# Witch.net
KiCad netlist of a schematic drawn in EAGLE
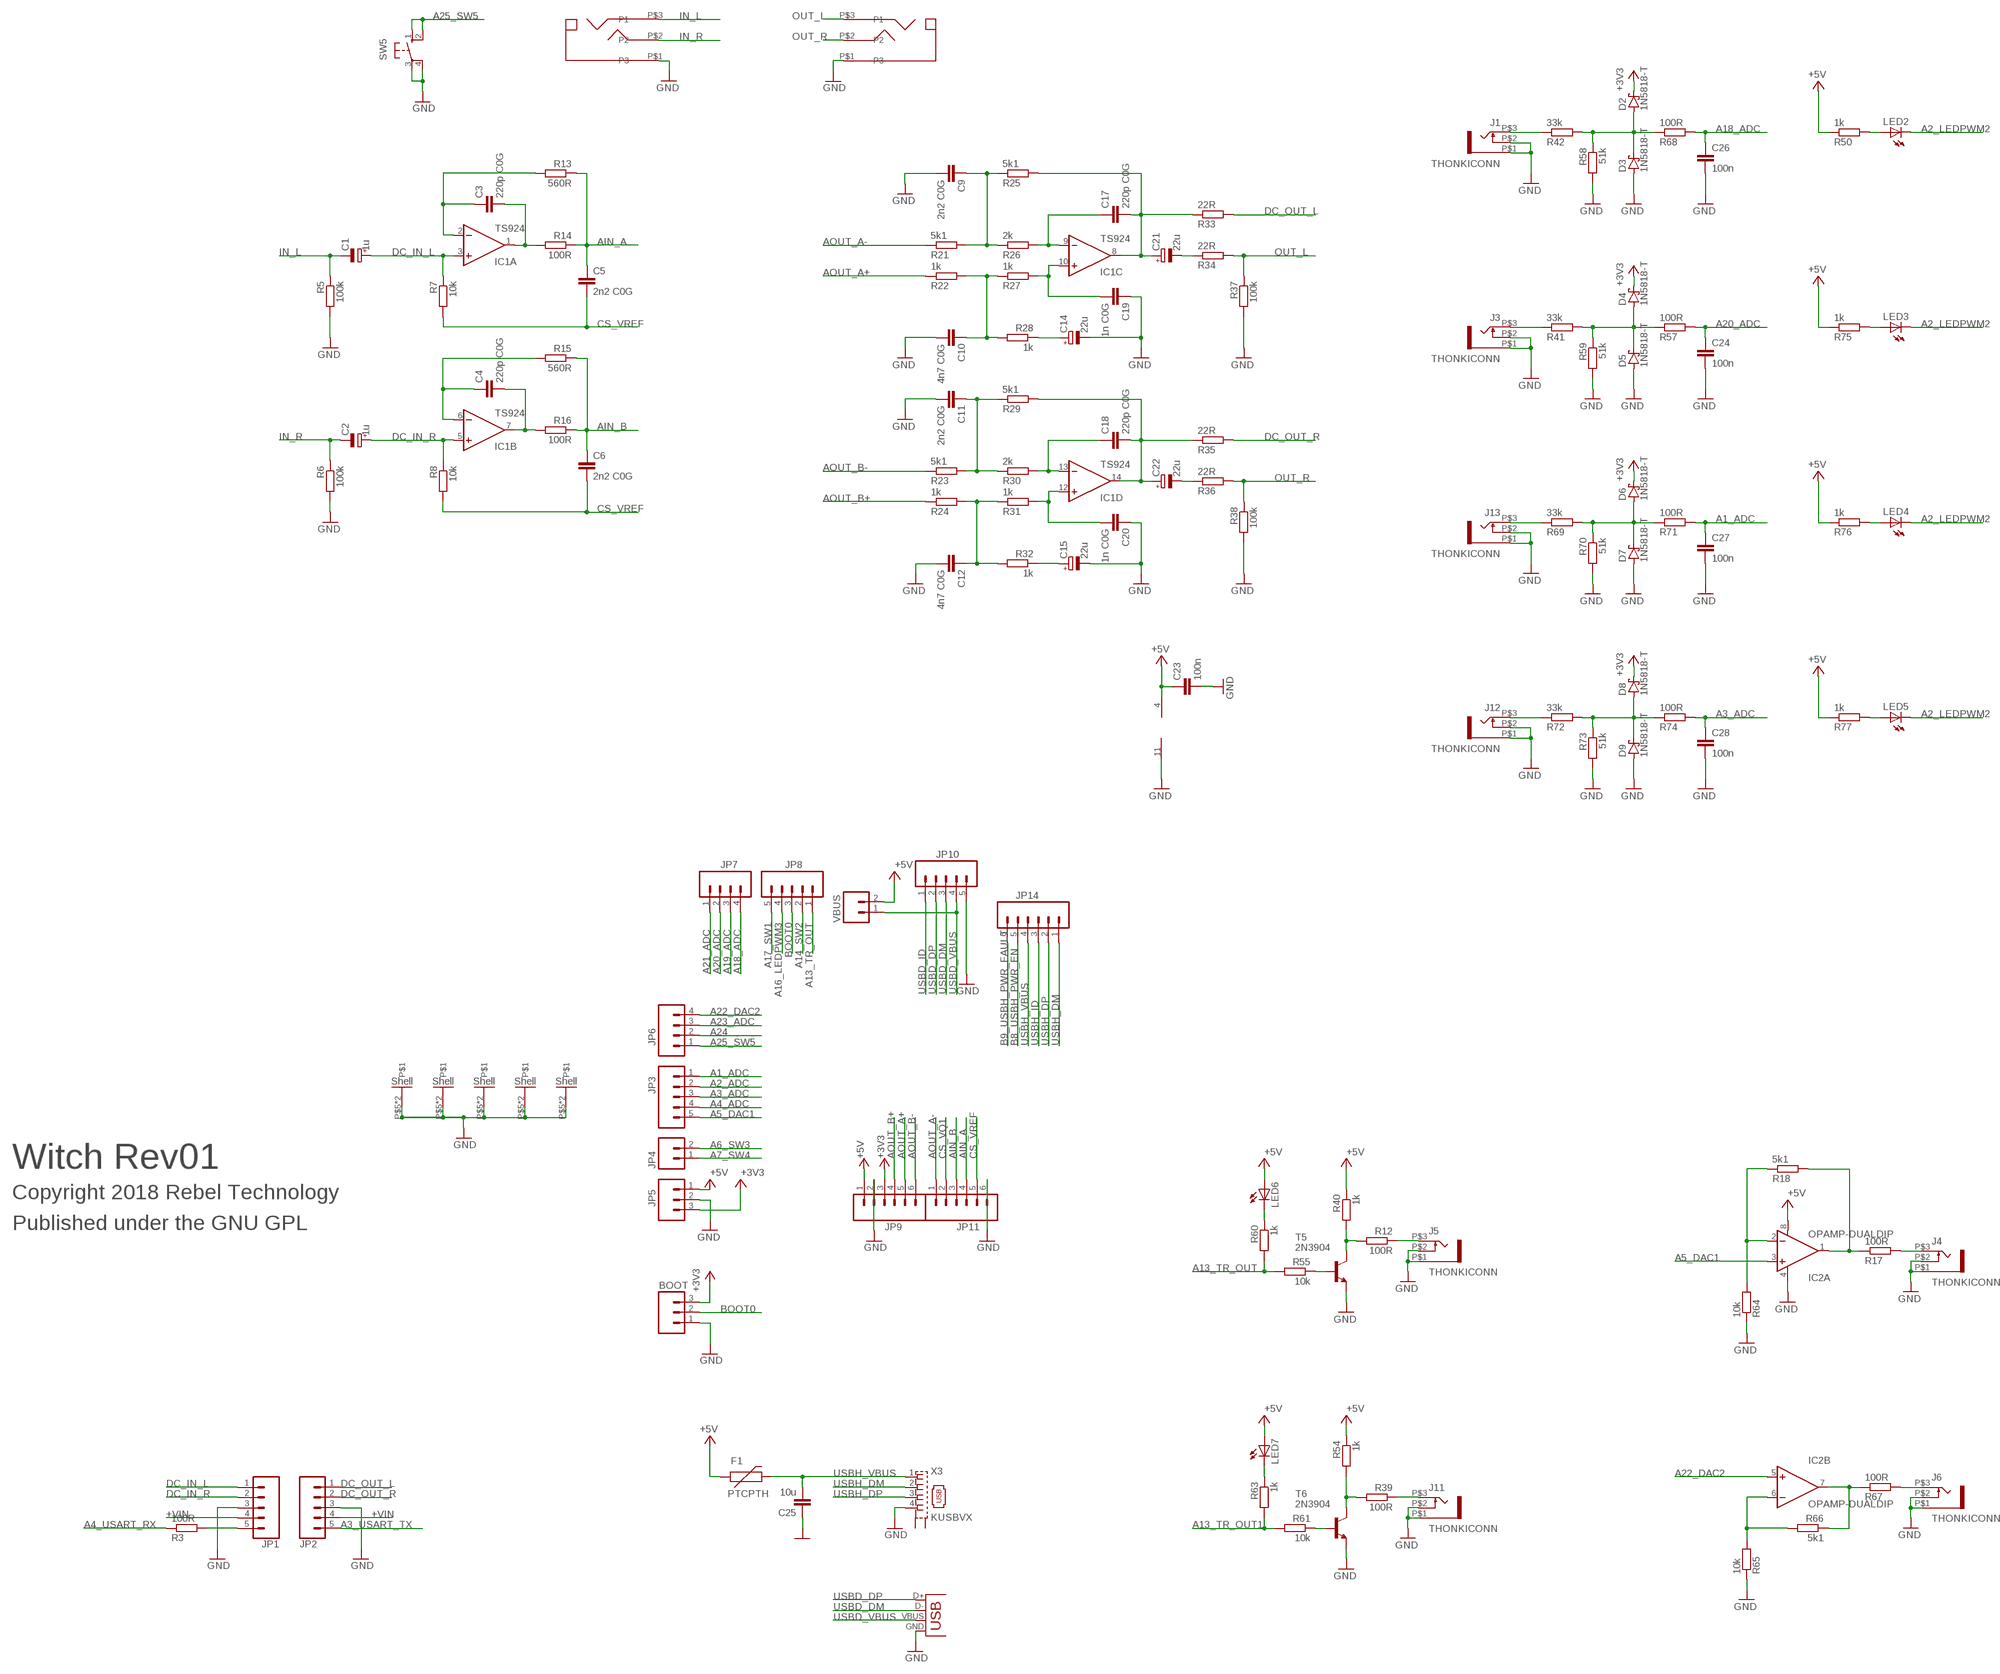
[diagram p0: schematic, sheet 1, part 1 of 2]
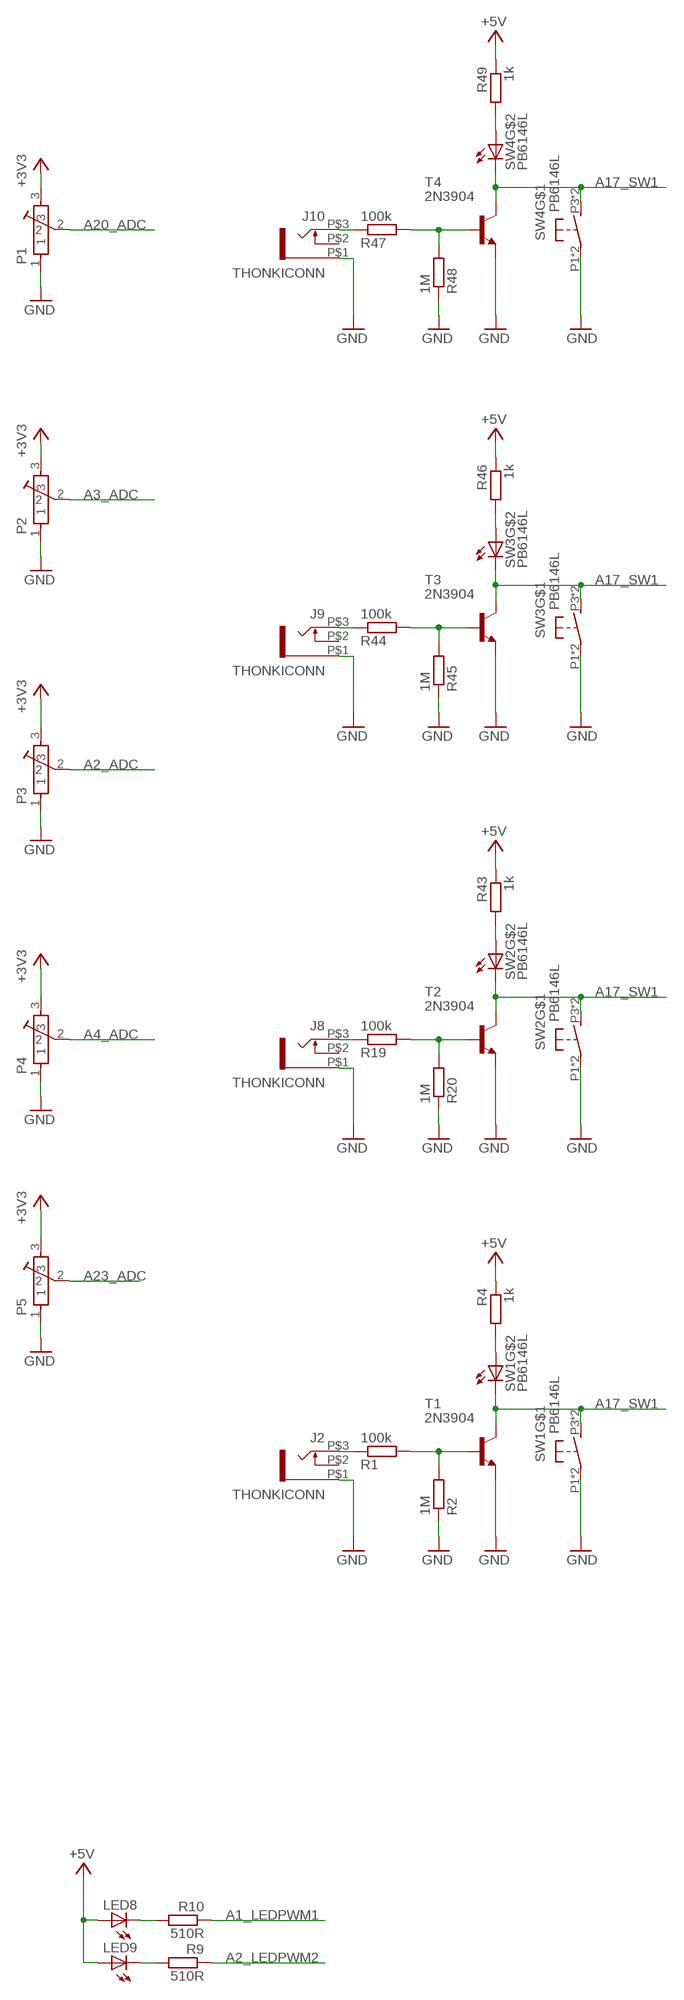
[diagram p1: schematic, sheet 1, part 2 of 2]

(export (version "E")
  (design (tool "Eeschema 10.0.6"))
  (components
    (comp (ref "BOOT")
      (value "M03PTH")
      (footprint "eagle-import:1X03")
      (libsource (lib "eagle-import") (part "M03PTH"))
    )
    (comp (ref "C1")
      (value "1u")
      (footprint "eagle-import:E5-6")
      (libsource (lib "eagle-import") (part "CPOL-EUE5-6"))
    )
    (comp (ref "C2")
      (value "1u")
      (footprint "eagle-import:E5-6")
      (libsource (lib "eagle-import") (part "CPOL-EUE5-6"))
    )
    (comp (ref "C3")
      (value "220p C0G")
      (footprint "eagle-import:C050-024X044")
      (libsource (lib "eagle-import") (part "C-EU050-024X044"))
    )
    (comp (ref "C4")
      (value "220p C0G")
      (footprint "eagle-import:C050-024X044")
      (libsource (lib "eagle-import") (part "C-EU050-024X044"))
    )
    (comp (ref "C5")
      (value "2n2 C0G")
      (footprint "eagle-import:C050-024X044")
      (libsource (lib "eagle-import") (part "C-EU050-024X044"))
    )
    (comp (ref "C6")
      (value "2n2 C0G")
      (footprint "eagle-import:C050-024X044")
      (libsource (lib "eagle-import") (part "C-EU050-024X044"))
    )
    (comp (ref "C9")
      (value "2n2 C0G")
      (footprint "eagle-import:C050-024X044")
      (libsource (lib "eagle-import") (part "C-EU050-024X044"))
    )
    (comp (ref "C10")
      (value "4n7 C0G")
      (footprint "eagle-import:C050-024X044")
      (libsource (lib "eagle-import") (part "C-EU050-024X044"))
    )
    (comp (ref "C11")
      (value "2n2 C0G")
      (footprint "eagle-import:C050-024X044")
      (libsource (lib "eagle-import") (part "C-EU050-024X044"))
    )
    (comp (ref "C12")
      (value "4n7 C0G")
      (footprint "eagle-import:C050-024X044")
      (libsource (lib "eagle-import") (part "C-EU050-024X044"))
    )
    (comp (ref "C14")
      (value "22u")
      (footprint "eagle-import:E5-6")
      (libsource (lib "eagle-import") (part "CPOL-EUE5-6"))
    )
    (comp (ref "C15")
      (value "22u")
      (footprint "eagle-import:E5-6")
      (libsource (lib "eagle-import") (part "CPOL-EUE5-6"))
    )
    (comp (ref "C17")
      (value "220p C0G")
      (footprint "eagle-import:C050-024X044")
      (libsource (lib "eagle-import") (part "C-EU050-024X044"))
    )
    (comp (ref "C18")
      (value "220p C0G")
      (footprint "eagle-import:C050-024X044")
      (libsource (lib "eagle-import") (part "C-EU050-024X044"))
    )
    (comp (ref "C19")
      (value "1n C0G")
      (footprint "eagle-import:C050-024X044")
      (libsource (lib "eagle-import") (part "C-EU050-024X044"))
    )
    (comp (ref "C20")
      (value "1n C0G")
      (footprint "eagle-import:C050-024X044")
      (libsource (lib "eagle-import") (part "C-EU050-024X044"))
    )
    (comp (ref "C21")
      (value "22u")
      (footprint "eagle-import:E5-6")
      (libsource (lib "eagle-import") (part "CPOL-EUE5-6"))
    )
    (comp (ref "C22")
      (value "22u")
      (footprint "eagle-import:E5-6")
      (libsource (lib "eagle-import") (part "CPOL-EUE5-6"))
    )
    (comp (ref "C23")
      (value "100n")
      (footprint "eagle-import:C050-024X044")
      (libsource (lib "eagle-import") (part "C-EU050-024X044"))
    )
    (comp (ref "C24")
      (value "100n")
      (footprint "eagle-import:C050-024X044")
      (libsource (lib "eagle-import") (part "C-EU050-024X044"))
    )
    (comp (ref "C25")
      (value "10u")
      (footprint "eagle-import:C050-024X044")
      (libsource (lib "eagle-import") (part "C-EU050-024X044"))
    )
    (comp (ref "C26")
      (value "100n")
      (footprint "eagle-import:C050-024X044")
      (libsource (lib "eagle-import") (part "C-EU050-024X044"))
    )
    (comp (ref "C27")
      (value "100n")
      (footprint "eagle-import:C050-024X044")
      (libsource (lib "eagle-import") (part "C-EU050-024X044"))
    )
    (comp (ref "C28")
      (value "100n")
      (footprint "eagle-import:C050-024X044")
      (libsource (lib "eagle-import") (part "C-EU050-024X044"))
    )
    (comp (ref "D2")
      (value "1N5818-T")
      (footprint "eagle-import:DO41-7.6")
      (libsource (lib "eagle-import") (part "1N5818-T"))
    )
    (comp (ref "D3")
      (value "1N5818-T")
      (footprint "eagle-import:DO41-7.6")
      (libsource (lib "eagle-import") (part "1N5818-T"))
    )
    (comp (ref "D4")
      (value "1N5818-T")
      (footprint "eagle-import:DO41-7.6")
      (libsource (lib "eagle-import") (part "1N5818-T"))
    )
    (comp (ref "D5")
      (value "1N5818-T")
      (footprint "eagle-import:DO41-7.6")
      (libsource (lib "eagle-import") (part "1N5818-T"))
    )
    (comp (ref "D6")
      (value "1N5818-T")
      (footprint "eagle-import:DO41-7.6")
      (libsource (lib "eagle-import") (part "1N5818-T"))
    )
    (comp (ref "D7")
      (value "1N5818-T")
      (footprint "eagle-import:DO41-7.6")
      (libsource (lib "eagle-import") (part "1N5818-T"))
    )
    (comp (ref "D8")
      (value "1N5818-T")
      (footprint "eagle-import:DO41-7.6")
      (libsource (lib "eagle-import") (part "1N5818-T"))
    )
    (comp (ref "D9")
      (value "1N5818-T")
      (footprint "eagle-import:DO41-7.6")
      (libsource (lib "eagle-import") (part "1N5818-T"))
    )
    (comp (ref "F1")
      (value "PTCPTH")
      (footprint "eagle-import:PTC")
      (libsource (lib "eagle-import") (part "PTCPTH"))
    )
    (comp (ref "IC1")
      (value "TS924")
      (footprint "eagle-import:DIL14")
      (libsource (lib "eagle-import") (part "LM324N"))
    )
    (comp (ref "IC2")
      (value "OPAMP-DUALDIP")
      (footprint "eagle-import:DIP08")
      (libsource (lib "eagle-import") (part "OPAMP-DUALDIP"))
    )
    (comp (ref "J1")
      (value "THONKICONN")
      (footprint "eagle-import:THONKICONN")
      (libsource (lib "eagle-import") (part "THONKICONN"))
    )
    (comp (ref "J2")
      (value "THONKICONN")
      (footprint "eagle-import:THONKICONN")
      (libsource (lib "eagle-import") (part "THONKICONN"))
    )
    (comp (ref "J3")
      (value "THONKICONN")
      (footprint "eagle-import:THONKICONN")
      (libsource (lib "eagle-import") (part "THONKICONN"))
    )
    (comp (ref "J4")
      (value "THONKICONN")
      (footprint "eagle-import:THONKICONN")
      (libsource (lib "eagle-import") (part "THONKICONN"))
    )
    (comp (ref "J5")
      (value "THONKICONN")
      (footprint "eagle-import:THONKICONN")
      (libsource (lib "eagle-import") (part "THONKICONN"))
    )
    (comp (ref "J6")
      (value "THONKICONN")
      (footprint "eagle-import:THONKICONN")
      (libsource (lib "eagle-import") (part "THONKICONN"))
    )
    (comp (ref "J8")
      (value "THONKICONN")
      (footprint "eagle-import:THONKICONN")
      (libsource (lib "eagle-import") (part "THONKICONN"))
    )
    (comp (ref "J9")
      (value "THONKICONN")
      (footprint "eagle-import:THONKICONN")
      (libsource (lib "eagle-import") (part "THONKICONN"))
    )
    (comp (ref "J10")
      (value "THONKICONN")
      (footprint "eagle-import:THONKICONN")
      (libsource (lib "eagle-import") (part "THONKICONN"))
    )
    (comp (ref "J11")
      (value "THONKICONN")
      (footprint "eagle-import:THONKICONN")
      (libsource (lib "eagle-import") (part "THONKICONN"))
    )
    (comp (ref "J12")
      (value "THONKICONN")
      (footprint "eagle-import:THONKICONN")
      (libsource (lib "eagle-import") (part "THONKICONN"))
    )
    (comp (ref "J13")
      (value "THONKICONN")
      (footprint "eagle-import:THONKICONN")
      (libsource (lib "eagle-import") (part "THONKICONN"))
    )
    (comp (ref "JP1")
      (value "CONN_05JST-VERT")
      (footprint "eagle-import:JST-5-PTH-VERT")
      (libsource (lib "eagle-import") (part "CONN_05JST-VERT"))
    )
    (comp (ref "JP2")
      (value "CONN_05JST-VERT")
      (footprint "eagle-import:JST-5-PTH-VERT")
      (libsource (lib "eagle-import") (part "CONN_05JST-VERT"))
    )
    (comp (ref "JP3")
      (value "M05PTH")
      (footprint "eagle-import:1X05")
      (libsource (lib "eagle-import") (part "M05PTH"))
    )
    (comp (ref "JP4")
      (value "M02PTH")
      (footprint "eagle-import:1X02")
      (libsource (lib "eagle-import") (part "M02PTH"))
    )
    (comp (ref "JP5")
      (value "M03PTH")
      (footprint "eagle-import:1X03")
      (libsource (lib "eagle-import") (part "M03PTH"))
    )
    (comp (ref "JP6")
      (value "M04PTH")
      (footprint "eagle-import:1X04")
      (libsource (lib "eagle-import") (part "M04PTH"))
    )
    (comp (ref "JP7")
      (value "M04PTH")
      (footprint "eagle-import:1X04")
      (libsource (lib "eagle-import") (part "M04PTH"))
    )
    (comp (ref "JP8")
      (value "M05PTH")
      (footprint "eagle-import:1X05")
      (libsource (lib "eagle-import") (part "M05PTH"))
    )
    (comp (ref "JP9")
      (value "M06SIP")
      (footprint "eagle-import:1X06")
      (libsource (lib "eagle-import") (part "M06SIP"))
    )
    (comp (ref "JP10")
      (value "M05PTH")
      (footprint "eagle-import:1X05")
      (libsource (lib "eagle-import") (part "M05PTH"))
    )
    (comp (ref "JP11")
      (value "M06SIP")
      (footprint "eagle-import:1X06")
      (libsource (lib "eagle-import") (part "M06SIP"))
    )
    (comp (ref "JP14")
      (value "M06SIP")
      (footprint "eagle-import:1X06")
      (libsource (lib "eagle-import") (part "M06SIP"))
    )
    (comp (ref "LED2")
      (value "LED3MM")
      (footprint "eagle-import:LED3MM")
      (libsource (lib "eagle-import") (part "LED3MM"))
    )
    (comp (ref "LED3")
      (value "LED3MM")
      (footprint "eagle-import:LED3MM")
      (libsource (lib "eagle-import") (part "LED3MM"))
    )
    (comp (ref "LED4")
      (value "LED3MM")
      (footprint "eagle-import:LED3MM")
      (libsource (lib "eagle-import") (part "LED3MM"))
    )
    (comp (ref "LED5")
      (value "LED3MM")
      (footprint "eagle-import:LED3MM")
      (libsource (lib "eagle-import") (part "LED3MM"))
    )
    (comp (ref "LED6")
      (value "LED3MM")
      (footprint "eagle-import:LED3MM")
      (libsource (lib "eagle-import") (part "LED3MM"))
    )
    (comp (ref "LED7")
      (value "LED3MM")
      (footprint "eagle-import:LED3MM")
      (libsource (lib "eagle-import") (part "LED3MM"))
    )
    (comp (ref "LED8")
      (value "LED3MM")
      (footprint "eagle-import:LED3MM")
      (libsource (lib "eagle-import") (part "LED3MM"))
    )
    (comp (ref "LED9")
      (value "LED3MM")
      (footprint "eagle-import:LED3MM")
      (libsource (lib "eagle-import") (part "LED3MM"))
    )
    (comp (ref "P1")
      (value "POT-ALPS-RK09L1140")
      (footprint "eagle-import:POT-ALPS-RK09L1140")
      (libsource (lib "eagle-import") (part "POT-ALPS-RK09L1140"))
    )
    (comp (ref "P2")
      (value "POT-ALPS-RK09L1140")
      (footprint "eagle-import:POT-ALPS-RK09L1140")
      (libsource (lib "eagle-import") (part "POT-ALPS-RK09L1140"))
    )
    (comp (ref "P3")
      (value "POT-ALPS-RK09L1140")
      (footprint "eagle-import:POT-ALPS-RK09L1140")
      (libsource (lib "eagle-import") (part "POT-ALPS-RK09L1140"))
    )
    (comp (ref "P4")
      (value "POT-ALPS-RK09L1140")
      (footprint "eagle-import:POT-ALPS-RK09L1140")
      (libsource (lib "eagle-import") (part "POT-ALPS-RK09L1140"))
    )
    (comp (ref "P5")
      (value "POT-ALPS-RK09L1140")
      (footprint "eagle-import:POT-ALPS-RK09L1140")
      (libsource (lib "eagle-import") (part "POT-ALPS-RK09L1140"))
    )
    (comp (ref "R1")
      (value "100k")
      (footprint "eagle-import:0204_7")
      (libsource (lib "eagle-import") (part "R-EU_0204/7"))
    )
    (comp (ref "R2")
      (value "1M")
      (footprint "eagle-import:0204_7")
      (libsource (lib "eagle-import") (part "R-EU_0204/7"))
    )
    (comp (ref "R3")
      (value "100R")
      (footprint "eagle-import:0204_7")
      (libsource (lib "eagle-import") (part "R-EU_0204/7"))
    )
    (comp (ref "R4")
      (value "1k")
      (footprint "eagle-import:0204_7")
      (libsource (lib "eagle-import") (part "R-EU_0204/7"))
    )
    (comp (ref "R5")
      (value "100k")
      (footprint "eagle-import:0204_7")
      (libsource (lib "eagle-import") (part "R-EU_0204/7"))
    )
    (comp (ref "R6")
      (value "100k")
      (footprint "eagle-import:0204_7")
      (libsource (lib "eagle-import") (part "R-EU_0204/7"))
    )
    (comp (ref "R7")
      (value "10k")
      (footprint "eagle-import:0204_7")
      (libsource (lib "eagle-import") (part "R-EU_0204/7"))
    )
    (comp (ref "R8")
      (value "10k")
      (footprint "eagle-import:0204_7")
      (libsource (lib "eagle-import") (part "R-EU_0204/7"))
    )
    (comp (ref "R9")
      (value "510R")
      (footprint "eagle-import:0204_7")
      (libsource (lib "eagle-import") (part "R-EU_0204/7"))
    )
    (comp (ref "R10")
      (value "510R")
      (footprint "eagle-import:0204_7")
      (libsource (lib "eagle-import") (part "R-EU_0204/7"))
    )
    (comp (ref "R12")
      (value "100R")
      (footprint "eagle-import:0204_7")
      (libsource (lib "eagle-import") (part "R-EU_0204/7"))
    )
    (comp (ref "R13")
      (value "560R")
      (footprint "eagle-import:0204_7")
      (libsource (lib "eagle-import") (part "R-EU_0204/7"))
    )
    (comp (ref "R14")
      (value "100R")
      (footprint "eagle-import:0204_7")
      (libsource (lib "eagle-import") (part "R-EU_0204/7"))
    )
    (comp (ref "R15")
      (value "560R")
      (footprint "eagle-import:0204_7")
      (libsource (lib "eagle-import") (part "R-EU_0204/7"))
    )
    (comp (ref "R16")
      (value "100R")
      (footprint "eagle-import:0204_7")
      (libsource (lib "eagle-import") (part "R-EU_0204/7"))
    )
    (comp (ref "R17")
      (value "100R")
      (footprint "eagle-import:0204_7")
      (libsource (lib "eagle-import") (part "R-EU_0204/7"))
    )
    (comp (ref "R18")
      (value "5k1")
      (footprint "eagle-import:0204_7")
      (libsource (lib "eagle-import") (part "R-EU_0204/7"))
    )
    (comp (ref "R19")
      (value "100k")
      (footprint "eagle-import:0204_7")
      (libsource (lib "eagle-import") (part "R-EU_0204/7"))
    )
    (comp (ref "R20")
      (value "1M")
      (footprint "eagle-import:0204_7")
      (libsource (lib "eagle-import") (part "R-EU_0204/7"))
    )
    (comp (ref "R21")
      (value "5k1")
      (footprint "eagle-import:0204_7")
      (libsource (lib "eagle-import") (part "R-EU_0204/7"))
    )
    (comp (ref "R22")
      (value "1k")
      (footprint "eagle-import:0204_7")
      (libsource (lib "eagle-import") (part "R-EU_0204/7"))
    )
    (comp (ref "R23")
      (value "5k1")
      (footprint "eagle-import:0204_7")
      (libsource (lib "eagle-import") (part "R-EU_0204/7"))
    )
    (comp (ref "R24")
      (value "1k")
      (footprint "eagle-import:0204_7")
      (libsource (lib "eagle-import") (part "R-EU_0204/7"))
    )
    (comp (ref "R25")
      (value "5k1")
      (footprint "eagle-import:0204_7")
      (libsource (lib "eagle-import") (part "R-EU_0204/7"))
    )
    (comp (ref "R26")
      (value "2k")
      (footprint "eagle-import:0204_7")
      (libsource (lib "eagle-import") (part "R-EU_0204/7"))
    )
    (comp (ref "R27")
      (value "1k")
      (footprint "eagle-import:0204_7")
      (libsource (lib "eagle-import") (part "R-EU_0204/7"))
    )
    (comp (ref "R28")
      (value "1k")
      (footprint "eagle-import:0204_7")
      (libsource (lib "eagle-import") (part "R-EU_0204/7"))
    )
    (comp (ref "R29")
      (value "5k1")
      (footprint "eagle-import:0204_7")
      (libsource (lib "eagle-import") (part "R-EU_0204/7"))
    )
    (comp (ref "R30")
      (value "2k")
      (footprint "eagle-import:0204_7")
      (libsource (lib "eagle-import") (part "R-EU_0204/7"))
    )
    (comp (ref "R31")
      (value "1k")
      (footprint "eagle-import:0204_7")
      (libsource (lib "eagle-import") (part "R-EU_0204/7"))
    )
    (comp (ref "R32")
      (value "1k")
      (footprint "eagle-import:0204_7")
      (libsource (lib "eagle-import") (part "R-EU_0204/7"))
    )
    (comp (ref "R33")
      (value "22R")
      (footprint "eagle-import:0204_7")
      (libsource (lib "eagle-import") (part "R-EU_0204/7"))
    )
    (comp (ref "R34")
      (value "22R")
      (footprint "eagle-import:0204_7")
      (libsource (lib "eagle-import") (part "R-EU_0204/7"))
    )
    (comp (ref "R35")
      (value "22R")
      (footprint "eagle-import:0204_7")
      (libsource (lib "eagle-import") (part "R-EU_0204/7"))
    )
    (comp (ref "R36")
      (value "22R")
      (footprint "eagle-import:0204_7")
      (libsource (lib "eagle-import") (part "R-EU_0204/7"))
    )
    (comp (ref "R37")
      (value "100k")
      (footprint "eagle-import:0204_7")
      (libsource (lib "eagle-import") (part "R-EU_0204/7"))
    )
    (comp (ref "R38")
      (value "100k")
      (footprint "eagle-import:0204_7")
      (libsource (lib "eagle-import") (part "R-EU_0204/7"))
    )
    (comp (ref "R39")
      (value "100R")
      (footprint "eagle-import:0204_7")
      (libsource (lib "eagle-import") (part "R-EU_0204/7"))
    )
    (comp (ref "R40")
      (value "1k")
      (footprint "eagle-import:0204_7")
      (libsource (lib "eagle-import") (part "R-EU_0204/7"))
    )
    (comp (ref "R41")
      (value "33k")
      (footprint "eagle-import:0204_7")
      (libsource (lib "eagle-import") (part "R-EU_0204/7"))
    )
    (comp (ref "R42")
      (value "33k")
      (footprint "eagle-import:0204_7")
      (libsource (lib "eagle-import") (part "R-EU_0204/7"))
    )
    (comp (ref "R43")
      (value "1k")
      (footprint "eagle-import:0204_7")
      (libsource (lib "eagle-import") (part "R-EU_0204/7"))
    )
    (comp (ref "R44")
      (value "100k")
      (footprint "eagle-import:0204_7")
      (libsource (lib "eagle-import") (part "R-EU_0204/7"))
    )
    (comp (ref "R45")
      (value "1M")
      (footprint "eagle-import:0204_7")
      (libsource (lib "eagle-import") (part "R-EU_0204/7"))
    )
    (comp (ref "R46")
      (value "1k")
      (footprint "eagle-import:0204_7")
      (libsource (lib "eagle-import") (part "R-EU_0204/7"))
    )
    (comp (ref "R47")
      (value "100k")
      (footprint "eagle-import:0204_7")
      (libsource (lib "eagle-import") (part "R-EU_0204/7"))
    )
    (comp (ref "R48")
      (value "1M")
      (footprint "eagle-import:0204_7")
      (libsource (lib "eagle-import") (part "R-EU_0204/7"))
    )
    (comp (ref "R49")
      (value "1k")
      (footprint "eagle-import:0204_7")
      (libsource (lib "eagle-import") (part "R-EU_0204/7"))
    )
    (comp (ref "R50")
      (value "1k")
      (footprint "eagle-import:0204_7")
      (libsource (lib "eagle-import") (part "R-EU_0204/7"))
    )
    (comp (ref "R54")
      (value "1k")
      (footprint "eagle-import:0204_7")
      (libsource (lib "eagle-import") (part "R-EU_0204/7"))
    )
    (comp (ref "R55")
      (value "10k")
      (footprint "eagle-import:0204_7")
      (libsource (lib "eagle-import") (part "R-EU_0204/7"))
    )
    (comp (ref "R57")
      (value "100R")
      (footprint "eagle-import:0204_7")
      (libsource (lib "eagle-import") (part "R-EU_0204/7"))
    )
    (comp (ref "R58")
      (value "51k")
      (footprint "eagle-import:0204_7")
      (libsource (lib "eagle-import") (part "R-EU_0204/7"))
    )
    (comp (ref "R59")
      (value "51k")
      (footprint "eagle-import:0204_7")
      (libsource (lib "eagle-import") (part "R-EU_0204/7"))
    )
    (comp (ref "R60")
      (value "1k")
      (footprint "eagle-import:0204_7")
      (libsource (lib "eagle-import") (part "R-EU_0204/7"))
    )
    (comp (ref "R61")
      (value "10k")
      (footprint "eagle-import:0204_7")
      (libsource (lib "eagle-import") (part "R-EU_0204/7"))
    )
    (comp (ref "R63")
      (value "1k")
      (footprint "eagle-import:0204_7")
      (libsource (lib "eagle-import") (part "R-EU_0204/7"))
    )
    (comp (ref "R64")
      (value "10k")
      (footprint "eagle-import:0204_7")
      (libsource (lib "eagle-import") (part "R-EU_0204/7"))
    )
    (comp (ref "R65")
      (value "10k")
      (footprint "eagle-import:0204_7")
      (libsource (lib "eagle-import") (part "R-EU_0204/7"))
    )
    (comp (ref "R66")
      (value "5k1")
      (footprint "eagle-import:0204_7")
      (libsource (lib "eagle-import") (part "R-EU_0204/7"))
    )
    (comp (ref "R67")
      (value "100R")
      (footprint "eagle-import:0204_7")
      (libsource (lib "eagle-import") (part "R-EU_0204/7"))
    )
    (comp (ref "R68")
      (value "100R")
      (footprint "eagle-import:0204_7")
      (libsource (lib "eagle-import") (part "R-EU_0204/7"))
    )
    (comp (ref "R69")
      (value "33k")
      (footprint "eagle-import:0204_7")
      (libsource (lib "eagle-import") (part "R-EU_0204/7"))
    )
    (comp (ref "R70")
      (value "51k")
      (footprint "eagle-import:0204_7")
      (libsource (lib "eagle-import") (part "R-EU_0204/7"))
    )
    (comp (ref "R71")
      (value "100R")
      (footprint "eagle-import:0204_7")
      (libsource (lib "eagle-import") (part "R-EU_0204/7"))
    )
    (comp (ref "R72")
      (value "33k")
      (footprint "eagle-import:0204_7")
      (libsource (lib "eagle-import") (part "R-EU_0204/7"))
    )
    (comp (ref "R73")
      (value "51k")
      (footprint "eagle-import:0204_7")
      (libsource (lib "eagle-import") (part "R-EU_0204/7"))
    )
    (comp (ref "R74")
      (value "100R")
      (footprint "eagle-import:0204_7")
      (libsource (lib "eagle-import") (part "R-EU_0204/7"))
    )
    (comp (ref "R75")
      (value "1k")
      (footprint "eagle-import:0204_7")
      (libsource (lib "eagle-import") (part "R-EU_0204/7"))
    )
    (comp (ref "R76")
      (value "1k")
      (footprint "eagle-import:0204_7")
      (libsource (lib "eagle-import") (part "R-EU_0204/7"))
    )
    (comp (ref "R77")
      (value "1k")
      (footprint "eagle-import:0204_7")
      (libsource (lib "eagle-import") (part "R-EU_0204/7"))
    )
    (comp (ref "SW1")
      (value "PB6146L")
      (footprint "eagle-import:PB6146L")
      (libsource (lib "eagle-import") (part "PB6146L"))
    )
    (comp (ref "SW2")
      (value "PB6146L")
      (footprint "eagle-import:PB6146L")
      (libsource (lib "eagle-import") (part "PB6146L"))
    )
    (comp (ref "SW3")
      (value "PB6146L")
      (footprint "eagle-import:PB6146L")
      (libsource (lib "eagle-import") (part "PB6146L"))
    )
    (comp (ref "SW4")
      (value "PB6146L")
      (footprint "eagle-import:PB6146L")
      (libsource (lib "eagle-import") (part "PB6146L"))
    )
    (comp (ref "SW5")
      (value "10-XX")
      (footprint "eagle-import:B3F-10XX")
      (fields (field (name "MPN") "B3F-1000"))
      (libsource (lib "eagle-import") (part "10-XX"))
    )
    (comp (ref "T1")
      (value "2N3904")
      (footprint "eagle-import:TO92")
      (libsource (lib "eagle-import") (part "2N3904"))
    )
    (comp (ref "T2")
      (value "2N3904")
      (footprint "eagle-import:TO92")
      (libsource (lib "eagle-import") (part "2N3904"))
    )
    (comp (ref "T3")
      (value "2N3904")
      (footprint "eagle-import:TO92")
      (libsource (lib "eagle-import") (part "2N3904"))
    )
    (comp (ref "T4")
      (value "2N3904")
      (footprint "eagle-import:TO92")
      (libsource (lib "eagle-import") (part "2N3904"))
    )
    (comp (ref "T5")
      (value "2N3904")
      (footprint "eagle-import:TO92")
      (libsource (lib "eagle-import") (part "2N3904"))
    )
    (comp (ref "T6")
      (value "2N3904")
      (footprint "eagle-import:TO92")
      (libsource (lib "eagle-import") (part "2N3904"))
    )
    (comp (ref "U$4")
      (value "THONKICONN_STEREO")
      (footprint "eagle-import:THONKICONN_STEREO")
      (libsource (lib "eagle-import") (part "THONKICONN_STEREO"))
    )
    (comp (ref "U$5")
      (value "THONKICONN_STEREO")
      (footprint "eagle-import:THONKICONN_STEREO")
      (libsource (lib "eagle-import") (part "THONKICONN_STEREO"))
    )
    (comp (ref "VBUS")
      (value "M02PTH")
      (footprint "eagle-import:1X02")
      (libsource (lib "eagle-import") (part "M02PTH"))
    )
    (comp (ref "X3")
      (value "KUSBVX")
      (footprint "eagle-import:KUSBVX")
      (libsource (lib "eagle-import") (part "KUSBVX"))
    )
    (comp (ref "X5")
      (value "USBPTH-VERTICAL")
      (footprint "eagle-import:USB-B-PTH-VERTICAL")
      (libsource (lib "eagle-import") (part "USBPTH-VERTICAL"))
    )
  )
  (nets
    (net (code "1") (name "+3V3") (class "Default")
      (node (ref "BOOT") (pin "3") (pinfunction "3_3") (pintype "passive"))
      (node (ref "D2") (pin "C") (pinfunction "C_C") (pintype "passive"))
      (node (ref "D4") (pin "C") (pinfunction "C_C") (pintype "passive"))
      (node (ref "D6") (pin "C") (pinfunction "C_C") (pintype "passive"))
      (node (ref "D8") (pin "C") (pinfunction "C_C") (pintype "passive"))
      (node (ref "JP5") (pin "3") (pinfunction "3_3") (pintype "passive"))
      (node (ref "JP9") (pin "3") (pinfunction "3_3") (pintype "passive"))
      (node (ref "P1") (pin "3") (pinfunction "3_3") (pintype "bidirectional"))
      (node (ref "P2") (pin "3") (pinfunction "3_3") (pintype "bidirectional"))
      (node (ref "P3") (pin "3") (pinfunction "3_3") (pintype "bidirectional"))
      (node (ref "P4") (pin "3") (pinfunction "3_3") (pintype "bidirectional"))
      (node (ref "P5") (pin "3") (pinfunction "3_3") (pintype "bidirectional"))
    )
    (net (code "2") (name "+5V") (class "Default")
      (node (ref "C23") (pin "1") (pinfunction "1_1") (pintype "passive"))
      (node (ref "F1") (pin "P$1") (pinfunction "1_P$1") (pintype "bidirectional"))
      (node (ref "IC1") (pin "4") (pinfunction "V+_4") (pintype "power_in"))
      (node (ref "IC2") (pin "8") (pinfunction "V+_8") (pintype "power_in"))
      (node (ref "JP5") (pin "1") (pinfunction "1_1") (pintype "passive"))
      (node (ref "JP9") (pin "1") (pinfunction "1_1") (pintype "passive"))
      (node (ref "LED6") (pin "A") (pinfunction "A_A") (pintype "passive"))
      (node (ref "LED7") (pin "A") (pinfunction "A_A") (pintype "passive"))
      (node (ref "LED8") (pin "A") (pinfunction "A_A") (pintype "passive"))
      (node (ref "LED9") (pin "A") (pinfunction "A_A") (pintype "passive"))
      (node (ref "R4") (pin "1") (pinfunction "1_1") (pintype "passive"))
      (node (ref "R40") (pin "1") (pinfunction "1_1") (pintype "passive"))
      (node (ref "R43") (pin "1") (pinfunction "1_1") (pintype "passive"))
      (node (ref "R46") (pin "1") (pinfunction "1_1") (pintype "passive"))
      (node (ref "R49") (pin "1") (pinfunction "1_1") (pintype "passive"))
      (node (ref "R50") (pin "1") (pinfunction "1_1") (pintype "passive"))
      (node (ref "R54") (pin "1") (pinfunction "1_1") (pintype "passive"))
      (node (ref "R75") (pin "1") (pinfunction "1_1") (pintype "passive"))
      (node (ref "R76") (pin "1") (pinfunction "1_1") (pintype "passive"))
      (node (ref "R77") (pin "1") (pinfunction "1_1") (pintype "passive"))
      (node (ref "VBUS") (pin "2") (pinfunction "2_2") (pintype "passive"))
    )
    (net (code "3") (name "/+VIN") (class "Default")
      (node (ref "JP1") (pin "4") (pinfunction "4_4") (pintype "passive"))
      (node (ref "JP2") (pin "4") (pinfunction "4_4") (pintype "passive"))
    )
    (net (code "4") (name "/A1_ADC") (class "Default")
      (node (ref "C27") (pin "1") (pinfunction "1_1") (pintype "passive"))
      (node (ref "JP3") (pin "1") (pinfunction "1_1") (pintype "passive"))
      (node (ref "R71") (pin "2") (pinfunction "2_2") (pintype "passive"))
    )
    (net (code "5") (name "/A1_LEDPWM1") (class "Default")
      (node (ref "R10") (pin "1") (pinfunction "1_1") (pintype "passive"))
    )
    (net (code "6") (name "/A2_ADC") (class "Default")
      (node (ref "JP3") (pin "2") (pinfunction "2_2") (pintype "passive"))
      (node (ref "P3") (pin "2") (pinfunction "2_2") (pintype "bidirectional"))
    )
    (net (code "7") (name "/A2_LEDPWM2") (class "Default")
      (node (ref "LED2") (pin "K") (pinfunction "C_K") (pintype "passive"))
      (node (ref "LED3") (pin "K") (pinfunction "C_K") (pintype "passive"))
      (node (ref "LED4") (pin "K") (pinfunction "C_K") (pintype "passive"))
      (node (ref "LED5") (pin "K") (pinfunction "C_K") (pintype "passive"))
      (node (ref "R9") (pin "1") (pinfunction "1_1") (pintype "passive"))
    )
    (net (code "8") (name "/A3_ADC") (class "Default")
      (node (ref "C28") (pin "1") (pinfunction "1_1") (pintype "passive"))
      (node (ref "JP3") (pin "3") (pinfunction "3_3") (pintype "passive"))
      (node (ref "R74") (pin "2") (pinfunction "2_2") (pintype "passive"))
    )
    (net (code "9") (name "/A3_USART_TX") (class "Default")
      (node (ref "JP2") (pin "5") (pinfunction "5_5") (pintype "passive"))
    )
    (net (code "10") (name "/A4_ADC") (class "Default")
      (node (ref "JP3") (pin "4") (pinfunction "4_4") (pintype "passive"))
      (node (ref "P4") (pin "2") (pinfunction "2_2") (pintype "bidirectional"))
    )
    (net (code "11") (name "/A4_USART_RX") (class "Default")
      (node (ref "R3") (pin "1") (pinfunction "1_1") (pintype "passive"))
    )
    (net (code "12") (name "/A5_DAC1") (class "Default")
      (node (ref "IC2") (pin "3") (pinfunction "+IN_3") (pintype "input"))
      (node (ref "JP3") (pin "5") (pinfunction "5_5") (pintype "passive"))
    )
    (net (code "13") (name "/A6_SW3") (class "Default")
      (node (ref "JP4") (pin "2") (pinfunction "2_2") (pintype "passive"))
    )
    (net (code "14") (name "/A7_SW4") (class "Default")
      (node (ref "JP4") (pin "1") (pinfunction "1_1") (pintype "passive"))
    )
    (net (code "15") (name "/A13_TR_OUT") (class "Default")
      (node (ref "JP8") (pin "1") (pinfunction "1_1") (pintype "passive"))
      (node (ref "R55") (pin "2") (pinfunction "2_2") (pintype "passive"))
      (node (ref "R60") (pin "2") (pinfunction "2_2") (pintype "passive"))
    )
    (net (code "16") (name "/A13_TR_OUT1") (class "Default")
      (node (ref "R61") (pin "2") (pinfunction "2_2") (pintype "passive"))
      (node (ref "R63") (pin "2") (pinfunction "2_2") (pintype "passive"))
    )
    (net (code "17") (name "/A14_SW2") (class "Default")
      (node (ref "JP8") (pin "2") (pinfunction "2_2") (pintype "passive"))
    )
    (net (code "18") (name "/A16_LEDPWM3") (class "Default")
      (node (ref "JP8") (pin "4") (pinfunction "4_4") (pintype "passive"))
    )
    (net (code "19") (name "/A17_SW1") (class "Default")
      (node (ref "JP8") (pin "5") (pinfunction "5_5") (pintype "passive"))
      (node (ref "SW1") (pin "P3") (pinfunction "S_P3") (pintype "passive"))
      (node (ref "SW1") (pin "P4") (pinfunction "S_P4") (pintype "passive"))
      (node (ref "SW1") (pin "PL2") (pinfunction "C_PL2") (pintype "passive"))
      (node (ref "SW2") (pin "P3") (pinfunction "S_P3") (pintype "passive"))
      (node (ref "SW2") (pin "P4") (pinfunction "S_P4") (pintype "passive"))
      (node (ref "SW2") (pin "PL2") (pinfunction "C_PL2") (pintype "passive"))
      (node (ref "SW3") (pin "P3") (pinfunction "S_P3") (pintype "passive"))
      (node (ref "SW3") (pin "P4") (pinfunction "S_P4") (pintype "passive"))
      (node (ref "SW3") (pin "PL2") (pinfunction "C_PL2") (pintype "passive"))
      (node (ref "SW4") (pin "P3") (pinfunction "S_P3") (pintype "passive"))
      (node (ref "SW4") (pin "P4") (pinfunction "S_P4") (pintype "passive"))
      (node (ref "SW4") (pin "PL2") (pinfunction "C_PL2") (pintype "passive"))
      (node (ref "T1") (pin "1") (pinfunction "C_1") (pintype "passive"))
      (node (ref "T2") (pin "1") (pinfunction "C_1") (pintype "passive"))
      (node (ref "T3") (pin "1") (pinfunction "C_1") (pintype "passive"))
      (node (ref "T4") (pin "1") (pinfunction "C_1") (pintype "passive"))
    )
    (net (code "20") (name "/A18_ADC") (class "Default")
      (node (ref "C26") (pin "1") (pinfunction "1_1") (pintype "passive"))
      (node (ref "JP7") (pin "4") (pinfunction "4_4") (pintype "passive"))
      (node (ref "R68") (pin "2") (pinfunction "2_2") (pintype "passive"))
    )
    (net (code "21") (name "/A19_ADC") (class "Default")
      (node (ref "JP7") (pin "3") (pinfunction "3_3") (pintype "passive"))
      (node (ref "P1") (pin "2") (pinfunction "2_2") (pintype "bidirectional"))
    )
    (net (code "22") (name "/A20_ADC") (class "Default")
      (node (ref "C24") (pin "1") (pinfunction "1_1") (pintype "passive"))
      (node (ref "JP7") (pin "2") (pinfunction "2_2") (pintype "passive"))
      (node (ref "R57") (pin "2") (pinfunction "2_2") (pintype "passive"))
    )
    (net (code "23") (name "/A21_ADC") (class "Default")
      (node (ref "JP7") (pin "1") (pinfunction "1_1") (pintype "passive"))
      (node (ref "P2") (pin "2") (pinfunction "2_2") (pintype "bidirectional"))
    )
    (net (code "24") (name "/A22_DAC2") (class "Default")
      (node (ref "IC2") (pin "5") (pinfunction "+IN_5") (pintype "input"))
      (node (ref "JP6") (pin "4") (pinfunction "4_4") (pintype "passive"))
    )
    (net (code "25") (name "/A23_ADC") (class "Default")
      (node (ref "JP6") (pin "3") (pinfunction "3_3") (pintype "passive"))
      (node (ref "P5") (pin "2") (pinfunction "2_2") (pintype "bidirectional"))
    )
    (net (code "26") (name "/A24") (class "Default")
      (node (ref "JP6") (pin "2") (pinfunction "2_2") (pintype "passive"))
    )
    (net (code "27") (name "/A25_SW5") (class "Default")
      (node (ref "JP6") (pin "1") (pinfunction "1_1") (pintype "passive"))
      (node (ref "SW5") (pin "1") (pinfunction "S_1") (pintype "passive"))
      (node (ref "SW5") (pin "2") (pinfunction "S1_2") (pintype "passive"))
    )
    (net (code "28") (name "/AIN_A") (class "Default")
      (node (ref "C5") (pin "1") (pinfunction "1_1") (pintype "passive"))
      (node (ref "JP11") (pin "4") (pinfunction "4_4") (pintype "passive"))
      (node (ref "R13") (pin "1") (pinfunction "1_1") (pintype "passive"))
      (node (ref "R14") (pin "1") (pinfunction "1_1") (pintype "passive"))
    )
    (net (code "29") (name "/AIN_B") (class "Default")
      (node (ref "C6") (pin "1") (pinfunction "1_1") (pintype "passive"))
      (node (ref "JP11") (pin "3") (pinfunction "3_3") (pintype "passive"))
      (node (ref "R15") (pin "1") (pinfunction "1_1") (pintype "passive"))
      (node (ref "R16") (pin "1") (pinfunction "1_1") (pintype "passive"))
    )
    (net (code "30") (name "/AOUT_A+") (class "Default")
      (node (ref "JP9") (pin "5") (pinfunction "5_5") (pintype "passive"))
      (node (ref "R22") (pin "1") (pinfunction "1_1") (pintype "passive"))
    )
    (net (code "31") (name "/AOUT_A-") (class "Default")
      (node (ref "JP11") (pin "1") (pinfunction "1_1") (pintype "passive"))
      (node (ref "R21") (pin "1") (pinfunction "1_1") (pintype "passive"))
    )
    (net (code "32") (name "/AOUT_B+") (class "Default")
      (node (ref "JP9") (pin "4") (pinfunction "4_4") (pintype "passive"))
      (node (ref "R24") (pin "1") (pinfunction "1_1") (pintype "passive"))
    )
    (net (code "33") (name "/AOUT_B-") (class "Default")
      (node (ref "JP9") (pin "6") (pinfunction "6_6") (pintype "passive"))
      (node (ref "R23") (pin "1") (pinfunction "1_1") (pintype "passive"))
    )
    (net (code "34") (name "/B8_USBH_PWR_EN") (class "Default")
      (node (ref "JP14") (pin "5") (pinfunction "5_5") (pintype "passive"))
    )
    (net (code "35") (name "/B9_USBH_PWR_FAULT") (class "Default")
      (node (ref "JP14") (pin "6") (pinfunction "6_6") (pintype "passive"))
    )
    (net (code "36") (name "/BOOT0") (class "Default")
      (node (ref "BOOT") (pin "2") (pinfunction "2_2") (pintype "passive"))
      (node (ref "JP8") (pin "3") (pinfunction "3_3") (pintype "passive"))
    )
    (net (code "37") (name "/CS_VQ1") (class "Default")
      (node (ref "JP11") (pin "2") (pinfunction "2_2") (pintype "passive"))
    )
    (net (code "38") (name "/CS_VREF") (class "Default")
      (node (ref "C5") (pin "2") (pinfunction "2_2") (pintype "passive"))
      (node (ref "C6") (pin "2") (pinfunction "2_2") (pintype "passive"))
      (node (ref "JP11") (pin "5") (pinfunction "5_5") (pintype "passive"))
      (node (ref "R7") (pin "2") (pinfunction "2_2") (pintype "passive"))
      (node (ref "R8") (pin "2") (pinfunction "2_2") (pintype "passive"))
    )
    (net (code "39") (name "/DC_IN_L") (class "Default")
      (node (ref "C1") (pin "+") (pinfunction "+_+") (pintype "passive"))
      (node (ref "IC1") (pin "3") (pinfunction "+IN_3") (pintype "input"))
      (node (ref "JP1") (pin "1") (pinfunction "1_1") (pintype "passive"))
      (node (ref "R7") (pin "1") (pinfunction "1_1") (pintype "passive"))
    )
    (net (code "40") (name "/DC_IN_R") (class "Default")
      (node (ref "C2") (pin "+") (pinfunction "+_+") (pintype "passive"))
      (node (ref "IC1") (pin "5") (pinfunction "+IN_5") (pintype "input"))
      (node (ref "JP1") (pin "2") (pinfunction "2_2") (pintype "passive"))
      (node (ref "R8") (pin "1") (pinfunction "1_1") (pintype "passive"))
    )
    (net (code "41") (name "/DC_OUT_L") (class "Default")
      (node (ref "JP2") (pin "1") (pinfunction "1_1") (pintype "passive"))
      (node (ref "R33") (pin "2") (pinfunction "2_2") (pintype "passive"))
    )
    (net (code "42") (name "/DC_OUT_R") (class "Default")
      (node (ref "JP2") (pin "2") (pinfunction "2_2") (pintype "passive"))
      (node (ref "R35") (pin "2") (pinfunction "2_2") (pintype "passive"))
    )
    (net (code "43") (name "/IN_L") (class "Default")
      (node (ref "C1") (pin "-") (pinfunction "-_-") (pintype "passive"))
      (node (ref "R5") (pin "1") (pinfunction "1_1") (pintype "passive"))
      (node (ref "U$4") (pin "P$3") (pinfunction "P1_P$3") (pintype "bidirectional"))
    )
    (net (code "44") (name "/IN_R") (class "Default")
      (node (ref "C2") (pin "-") (pinfunction "-_-") (pintype "passive"))
      (node (ref "R6") (pin "1") (pinfunction "1_1") (pintype "passive"))
      (node (ref "U$4") (pin "P$2") (pinfunction "P2_P$2") (pintype "bidirectional"))
    )
    (net (code "45") (name "/OUT_L") (class "Default")
      (node (ref "R34") (pin "2") (pinfunction "2_2") (pintype "passive"))
      (node (ref "R37") (pin "1") (pinfunction "1_1") (pintype "passive"))
      (node (ref "U$5") (pin "P$3") (pinfunction "P1_P$3") (pintype "bidirectional"))
    )
    (net (code "46") (name "/OUT_R") (class "Default")
      (node (ref "R36") (pin "2") (pinfunction "2_2") (pintype "passive"))
      (node (ref "R38") (pin "1") (pinfunction "1_1") (pintype "passive"))
      (node (ref "U$5") (pin "P$2") (pinfunction "P2_P$2") (pintype "bidirectional"))
    )
    (net (code "47") (name "/USBD_DM") (class "Default")
      (node (ref "JP10") (pin "3") (pinfunction "3_3") (pintype "passive"))
      (node (ref "X5") (pin "D-") (pinfunction "D-_D-") (pintype "bidirectional"))
    )
    (net (code "48") (name "/USBD_DP") (class "Default")
      (node (ref "JP10") (pin "2") (pinfunction "2_2") (pintype "passive"))
      (node (ref "X5") (pin "D+") (pinfunction "D+_D+") (pintype "bidirectional"))
    )
    (net (code "49") (name "/USBD_ID") (class "Default")
      (node (ref "JP10") (pin "1") (pinfunction "1_1") (pintype "passive"))
    )
    (net (code "50") (name "/USBD_VBUS") (class "Default")
      (node (ref "JP10") (pin "4") (pinfunction "4_4") (pintype "passive"))
      (node (ref "VBUS") (pin "1") (pinfunction "1_1") (pintype "passive"))
      (node (ref "X5") (pin "VBUS") (pinfunction "VBUS_VBUS") (pintype "bidirectional"))
    )
    (net (code "51") (name "/USBH_DM") (class "Default")
      (node (ref "JP14") (pin "1") (pinfunction "1_1") (pintype "passive"))
      (node (ref "X3") (pin "2") (pinfunction "2_2") (pintype "passive"))
    )
    (net (code "52") (name "/USBH_DP") (class "Default")
      (node (ref "JP14") (pin "2") (pinfunction "2_2") (pintype "passive"))
      (node (ref "X3") (pin "3") (pinfunction "3_3") (pintype "passive"))
    )
    (net (code "53") (name "/USBH_ID") (class "Default")
      (node (ref "JP14") (pin "3") (pinfunction "3_3") (pintype "passive"))
    )
    (net (code "54") (name "/USBH_VBUS") (class "Default")
      (node (ref "C25") (pin "2") (pinfunction "2_2") (pintype "passive"))
      (node (ref "F1") (pin "P$2") (pinfunction "2_P$2") (pintype "bidirectional"))
      (node (ref "JP14") (pin "4") (pinfunction "4_4") (pintype "passive"))
      (node (ref "X3") (pin "1") (pinfunction "1_1") (pintype "passive"))
    )
    (net (code "55") (name "GND") (class "Default")
      (node (ref "BOOT") (pin "1") (pinfunction "1_1") (pintype "passive"))
      (node (ref "C10") (pin "2") (pinfunction "2_2") (pintype "passive"))
      (node (ref "C11") (pin "2") (pinfunction "2_2") (pintype "passive"))
      (node (ref "C12") (pin "2") (pinfunction "2_2") (pintype "passive"))
      (node (ref "C14") (pin "-") (pinfunction "-_-") (pintype "passive"))
      (node (ref "C15") (pin "-") (pinfunction "-_-") (pintype "passive"))
      (node (ref "C19") (pin "1") (pinfunction "1_1") (pintype "passive"))
      (node (ref "C20") (pin "1") (pinfunction "1_1") (pintype "passive"))
      (node (ref "C23") (pin "2") (pinfunction "2_2") (pintype "passive"))
      (node (ref "C24") (pin "2") (pinfunction "2_2") (pintype "passive"))
      (node (ref "C25") (pin "1") (pinfunction "1_1") (pintype "passive"))
      (node (ref "C26") (pin "2") (pinfunction "2_2") (pintype "passive"))
      (node (ref "C27") (pin "2") (pinfunction "2_2") (pintype "passive"))
      (node (ref "C28") (pin "2") (pinfunction "2_2") (pintype "passive"))
      (node (ref "C9") (pin "2") (pinfunction "2_2") (pintype "passive"))
      (node (ref "D3") (pin "A") (pinfunction "A_A") (pintype "passive"))
      (node (ref "D5") (pin "A") (pinfunction "A_A") (pintype "passive"))
      (node (ref "D7") (pin "A") (pinfunction "A_A") (pintype "passive"))
      (node (ref "D9") (pin "A") (pinfunction "A_A") (pintype "passive"))
      (node (ref "IC1") (pin "11") (pinfunction "V-_11") (pintype "power_in"))
      (node (ref "IC2") (pin "4") (pinfunction "V-_4") (pintype "power_in"))
      (node (ref "J1") (pin "P$1") (pinfunction "5_P$1") (pintype "passive"))
      (node (ref "J1") (pin "P$2") (pinfunction "4_P$2") (pintype "passive"))
      (node (ref "J10") (pin "P$1") (pinfunction "5_P$1") (pintype "passive"))
      (node (ref "J11") (pin "P$1") (pinfunction "5_P$1") (pintype "passive"))
      (node (ref "J11") (pin "P$2") (pinfunction "4_P$2") (pintype "passive"))
      (node (ref "J12") (pin "P$1") (pinfunction "5_P$1") (pintype "passive"))
      (node (ref "J12") (pin "P$2") (pinfunction "4_P$2") (pintype "passive"))
      (node (ref "J13") (pin "P$1") (pinfunction "5_P$1") (pintype "passive"))
      (node (ref "J13") (pin "P$2") (pinfunction "4_P$2") (pintype "passive"))
      (node (ref "J2") (pin "P$1") (pinfunction "5_P$1") (pintype "passive"))
      (node (ref "J3") (pin "P$1") (pinfunction "5_P$1") (pintype "passive"))
      (node (ref "J3") (pin "P$2") (pinfunction "4_P$2") (pintype "passive"))
      (node (ref "J4") (pin "P$1") (pinfunction "5_P$1") (pintype "passive"))
      (node (ref "J4") (pin "P$2") (pinfunction "4_P$2") (pintype "passive"))
      (node (ref "J5") (pin "P$1") (pinfunction "5_P$1") (pintype "passive"))
      (node (ref "J5") (pin "P$2") (pinfunction "4_P$2") (pintype "passive"))
      (node (ref "J6") (pin "P$1") (pinfunction "5_P$1") (pintype "passive"))
      (node (ref "J6") (pin "P$2") (pinfunction "4_P$2") (pintype "passive"))
      (node (ref "J8") (pin "P$1") (pinfunction "5_P$1") (pintype "passive"))
      (node (ref "J9") (pin "P$1") (pinfunction "5_P$1") (pintype "passive"))
      (node (ref "JP1") (pin "3") (pinfunction "3_3") (pintype "passive"))
      (node (ref "JP10") (pin "5") (pinfunction "5_5") (pintype "passive"))
      (node (ref "JP11") (pin "6") (pinfunction "6_6") (pintype "passive"))
      (node (ref "JP2") (pin "3") (pinfunction "3_3") (pintype "passive"))
      (node (ref "JP5") (pin "2") (pinfunction "2_2") (pintype "passive"))
      (node (ref "JP9") (pin "2") (pinfunction "2_2") (pintype "passive"))
      (node (ref "P1") (pin "1") (pinfunction "1_1") (pintype "bidirectional"))
      (node (ref "P1") (pin "P$5") (pinfunction "P$1_P$5") (pintype "bidirectional"))
      (node (ref "P1") (pin "P$6") (pinfunction "P$1_P$6") (pintype "bidirectional"))
      (node (ref "P2") (pin "1") (pinfunction "1_1") (pintype "bidirectional"))
      (node (ref "P2") (pin "P$5") (pinfunction "P$1_P$5") (pintype "bidirectional"))
      (node (ref "P2") (pin "P$6") (pinfunction "P$1_P$6") (pintype "bidirectional"))
      (node (ref "P3") (pin "1") (pinfunction "1_1") (pintype "bidirectional"))
      (node (ref "P3") (pin "P$5") (pinfunction "P$1_P$5") (pintype "bidirectional"))
      (node (ref "P3") (pin "P$6") (pinfunction "P$1_P$6") (pintype "bidirectional"))
      (node (ref "P4") (pin "1") (pinfunction "1_1") (pintype "bidirectional"))
      (node (ref "P4") (pin "P$5") (pinfunction "P$1_P$5") (pintype "bidirectional"))
      (node (ref "P4") (pin "P$6") (pinfunction "P$1_P$6") (pintype "bidirectional"))
      (node (ref "P5") (pin "1") (pinfunction "1_1") (pintype "bidirectional"))
      (node (ref "P5") (pin "P$5") (pinfunction "P$1_P$5") (pintype "bidirectional"))
      (node (ref "P5") (pin "P$6") (pinfunction "P$1_P$6") (pintype "bidirectional"))
      (node (ref "R2") (pin "1") (pinfunction "1_1") (pintype "passive"))
      (node (ref "R20") (pin "1") (pinfunction "1_1") (pintype "passive"))
      (node (ref "R37") (pin "2") (pinfunction "2_2") (pintype "passive"))
      (node (ref "R38") (pin "2") (pinfunction "2_2") (pintype "passive"))
      (node (ref "R45") (pin "1") (pinfunction "1_1") (pintype "passive"))
      (node (ref "R48") (pin "1") (pinfunction "1_1") (pintype "passive"))
      (node (ref "R5") (pin "2") (pinfunction "2_2") (pintype "passive"))
      (node (ref "R58") (pin "2") (pinfunction "2_2") (pintype "passive"))
      (node (ref "R59") (pin "2") (pinfunction "2_2") (pintype "passive"))
      (node (ref "R6") (pin "2") (pinfunction "2_2") (pintype "passive"))
      (node (ref "R64") (pin "1") (pinfunction "1_1") (pintype "passive"))
      (node (ref "R65") (pin "1") (pinfunction "1_1") (pintype "passive"))
      (node (ref "R70") (pin "2") (pinfunction "2_2") (pintype "passive"))
      (node (ref "R73") (pin "2") (pinfunction "2_2") (pintype "passive"))
      (node (ref "SW1") (pin "P1") (pinfunction "P_P1") (pintype "passive"))
      (node (ref "SW1") (pin "P2") (pinfunction "P_P2") (pintype "passive"))
      (node (ref "SW2") (pin "P1") (pinfunction "P_P1") (pintype "passive"))
      (node (ref "SW2") (pin "P2") (pinfunction "P_P2") (pintype "passive"))
      (node (ref "SW3") (pin "P1") (pinfunction "P_P1") (pintype "passive"))
      (node (ref "SW3") (pin "P2") (pinfunction "P_P2") (pintype "passive"))
      (node (ref "SW4") (pin "P1") (pinfunction "P_P1") (pintype "passive"))
      (node (ref "SW4") (pin "P2") (pinfunction "P_P2") (pintype "passive"))
      (node (ref "SW5") (pin "3") (pinfunction "P_3") (pintype "passive"))
      (node (ref "SW5") (pin "4") (pinfunction "P1_4") (pintype "passive"))
      (node (ref "T1") (pin "3") (pinfunction "E_3") (pintype "passive"))
      (node (ref "T2") (pin "3") (pinfunction "E_3") (pintype "passive"))
      (node (ref "T3") (pin "3") (pinfunction "E_3") (pintype "passive"))
      (node (ref "T4") (pin "3") (pinfunction "E_3") (pintype "passive"))
      (node (ref "T5") (pin "3") (pinfunction "E_3") (pintype "passive"))
      (node (ref "T6") (pin "3") (pinfunction "E_3") (pintype "passive"))
      (node (ref "U$4") (pin "P$1") (pinfunction "P3_P$1") (pintype "bidirectional"))
      (node (ref "U$5") (pin "P$1") (pinfunction "P3_P$1") (pintype "bidirectional"))
      (node (ref "X3") (pin "4") (pinfunction "4_4") (pintype "passive"))
      (node (ref "X5") (pin "GND") (pinfunction "GND_GND") (pintype "bidirectional"))
    )
    (net (code "56") (name "Net-(C9-Pad1)") (class "Default")
      (node (ref "C9") (pin "1") (pinfunction "1_1") (pintype "passive"))
      (node (ref "R21") (pin "2") (pinfunction "2_2") (pintype "passive"))
      (node (ref "R25") (pin "1") (pinfunction "1_1") (pintype "passive"))
      (node (ref "R26") (pin "1") (pinfunction "1_1") (pintype "passive"))
    )
    (net (code "57") (name "Net-(C10-Pad1)") (class "Default")
      (node (ref "C10") (pin "1") (pinfunction "1_1") (pintype "passive"))
      (node (ref "R22") (pin "2") (pinfunction "2_2") (pintype "passive"))
      (node (ref "R27") (pin "1") (pinfunction "1_1") (pintype "passive"))
      (node (ref "R28") (pin "2") (pinfunction "2_2") (pintype "passive"))
    )
    (net (code "58") (name "Net-(C11-Pad1)") (class "Default")
      (node (ref "C11") (pin "1") (pinfunction "1_1") (pintype "passive"))
      (node (ref "R23") (pin "2") (pinfunction "2_2") (pintype "passive"))
      (node (ref "R29") (pin "1") (pinfunction "1_1") (pintype "passive"))
      (node (ref "R30") (pin "1") (pinfunction "1_1") (pintype "passive"))
    )
    (net (code "59") (name "Net-(C12-Pad1)") (class "Default")
      (node (ref "C12") (pin "1") (pinfunction "1_1") (pintype "passive"))
      (node (ref "R24") (pin "2") (pinfunction "2_2") (pintype "passive"))
      (node (ref "R31") (pin "1") (pinfunction "1_1") (pintype "passive"))
      (node (ref "R32") (pin "2") (pinfunction "2_2") (pintype "passive"))
    )
    (net (code "60") (name "Net-(C14-Pad+)") (class "Default")
      (node (ref "C14") (pin "+") (pinfunction "+_+") (pintype "passive"))
      (node (ref "R28") (pin "1") (pinfunction "1_1") (pintype "passive"))
    )
    (net (code "61") (name "Net-(C15-Pad+)") (class "Default")
      (node (ref "C15") (pin "+") (pinfunction "+_+") (pintype "passive"))
      (node (ref "R32") (pin "1") (pinfunction "1_1") (pintype "passive"))
    )
    (net (code "62") (name "Net-(C21-Pad-)") (class "Default")
      (node (ref "C21") (pin "-") (pinfunction "-_-") (pintype "passive"))
      (node (ref "R34") (pin "1") (pinfunction "1_1") (pintype "passive"))
    )
    (net (code "63") (name "Net-(C22-Pad-)") (class "Default")
      (node (ref "C22") (pin "-") (pinfunction "-_-") (pintype "passive"))
      (node (ref "R36") (pin "1") (pinfunction "1_1") (pintype "passive"))
    )
    (net (code "64") (name "Net-(D2-PadA)") (class "Default")
      (node (ref "D2") (pin "A") (pinfunction "A_A") (pintype "passive"))
      (node (ref "D3") (pin "C") (pinfunction "C_C") (pintype "passive"))
      (node (ref "R42") (pin "2") (pinfunction "2_2") (pintype "passive"))
      (node (ref "R58") (pin "1") (pinfunction "1_1") (pintype "passive"))
      (node (ref "R68") (pin "1") (pinfunction "1_1") (pintype "passive"))
    )
    (net (code "65") (name "Net-(D4-PadA)") (class "Default")
      (node (ref "D4") (pin "A") (pinfunction "A_A") (pintype "passive"))
      (node (ref "D5") (pin "C") (pinfunction "C_C") (pintype "passive"))
      (node (ref "R41") (pin "2") (pinfunction "2_2") (pintype "passive"))
      (node (ref "R57") (pin "1") (pinfunction "1_1") (pintype "passive"))
      (node (ref "R59") (pin "1") (pinfunction "1_1") (pintype "passive"))
    )
    (net (code "66") (name "Net-(D6-PadA)") (class "Default")
      (node (ref "D6") (pin "A") (pinfunction "A_A") (pintype "passive"))
      (node (ref "D7") (pin "C") (pinfunction "C_C") (pintype "passive"))
      (node (ref "R69") (pin "2") (pinfunction "2_2") (pintype "passive"))
      (node (ref "R70") (pin "1") (pinfunction "1_1") (pintype "passive"))
      (node (ref "R71") (pin "1") (pinfunction "1_1") (pintype "passive"))
    )
    (net (code "67") (name "Net-(D8-PadA)") (class "Default")
      (node (ref "D8") (pin "A") (pinfunction "A_A") (pintype "passive"))
      (node (ref "D9") (pin "C") (pinfunction "C_C") (pintype "passive"))
      (node (ref "R72") (pin "2") (pinfunction "2_2") (pintype "passive"))
      (node (ref "R73") (pin "1") (pinfunction "1_1") (pintype "passive"))
      (node (ref "R74") (pin "1") (pinfunction "1_1") (pintype "passive"))
    )
    (net (code "68") (name "Net-(IC1A--IN)") (class "Default")
      (node (ref "C3") (pin "1") (pinfunction "1_1") (pintype "passive"))
      (node (ref "IC1") (pin "2") (pinfunction "-IN_2") (pintype "input"))
      (node (ref "R13") (pin "2") (pinfunction "2_2") (pintype "passive"))
    )
    (net (code "69") (name "Net-(IC1A-OUT)") (class "Default")
      (node (ref "C3") (pin "2") (pinfunction "2_2") (pintype "passive"))
      (node (ref "IC1") (pin "1") (pinfunction "OUT_1") (pintype "output"))
      (node (ref "R14") (pin "2") (pinfunction "2_2") (pintype "passive"))
    )
    (net (code "70") (name "Net-(IC1B--IN)") (class "Default")
      (node (ref "C4") (pin "1") (pinfunction "1_1") (pintype "passive"))
      (node (ref "IC1") (pin "6") (pinfunction "-IN_6") (pintype "input"))
      (node (ref "R15") (pin "2") (pinfunction "2_2") (pintype "passive"))
    )
    (net (code "71") (name "Net-(IC1B-OUT)") (class "Default")
      (node (ref "C4") (pin "2") (pinfunction "2_2") (pintype "passive"))
      (node (ref "IC1") (pin "7") (pinfunction "OUT_7") (pintype "output"))
      (node (ref "R16") (pin "2") (pinfunction "2_2") (pintype "passive"))
    )
    (net (code "72") (name "Net-(IC1C-+IN)") (class "Default")
      (node (ref "C19") (pin "2") (pinfunction "2_2") (pintype "passive"))
      (node (ref "IC1") (pin "10") (pinfunction "+IN_10") (pintype "input"))
      (node (ref "R27") (pin "2") (pinfunction "2_2") (pintype "passive"))
    )
    (net (code "73") (name "Net-(IC1C--IN)") (class "Default")
      (node (ref "C17") (pin "1") (pinfunction "1_1") (pintype "passive"))
      (node (ref "IC1") (pin "9") (pinfunction "-IN_9") (pintype "input"))
      (node (ref "R26") (pin "2") (pinfunction "2_2") (pintype "passive"))
    )
    (net (code "74") (name "Net-(IC1C-OUT)") (class "Default")
      (node (ref "C17") (pin "2") (pinfunction "2_2") (pintype "passive"))
      (node (ref "C21") (pin "+") (pinfunction "+_+") (pintype "passive"))
      (node (ref "IC1") (pin "8") (pinfunction "OUT_8") (pintype "output"))
      (node (ref "R25") (pin "2") (pinfunction "2_2") (pintype "passive"))
      (node (ref "R33") (pin "1") (pinfunction "1_1") (pintype "passive"))
    )
    (net (code "75") (name "Net-(IC1D-+IN)") (class "Default")
      (node (ref "C20") (pin "2") (pinfunction "2_2") (pintype "passive"))
      (node (ref "IC1") (pin "12") (pinfunction "+IN_12") (pintype "input"))
      (node (ref "R31") (pin "2") (pinfunction "2_2") (pintype "passive"))
    )
    (net (code "76") (name "Net-(IC1D--IN)") (class "Default")
      (node (ref "C18") (pin "1") (pinfunction "1_1") (pintype "passive"))
      (node (ref "IC1") (pin "13") (pinfunction "-IN_13") (pintype "input"))
      (node (ref "R30") (pin "2") (pinfunction "2_2") (pintype "passive"))
    )
    (net (code "77") (name "Net-(IC1D-OUT)") (class "Default")
      (node (ref "C18") (pin "2") (pinfunction "2_2") (pintype "passive"))
      (node (ref "C22") (pin "+") (pinfunction "+_+") (pintype "passive"))
      (node (ref "IC1") (pin "14") (pinfunction "OUT_14") (pintype "output"))
      (node (ref "R29") (pin "2") (pinfunction "2_2") (pintype "passive"))
      (node (ref "R35") (pin "1") (pinfunction "1_1") (pintype "passive"))
    )
    (net (code "78") (name "Net-(IC2A--IN)") (class "Default")
      (node (ref "IC2") (pin "2") (pinfunction "-IN_2") (pintype "input"))
      (node (ref "R18") (pin "1") (pinfunction "1_1") (pintype "passive"))
      (node (ref "R64") (pin "2") (pinfunction "2_2") (pintype "passive"))
    )
    (net (code "79") (name "Net-(IC2A-OUT)") (class "Default")
      (node (ref "IC2") (pin "1") (pinfunction "OUT_1") (pintype "output"))
      (node (ref "R17") (pin "1") (pinfunction "1_1") (pintype "passive"))
      (node (ref "R18") (pin "2") (pinfunction "2_2") (pintype "passive"))
    )
    (net (code "80") (name "Net-(IC2B--IN)") (class "Default")
      (node (ref "IC2") (pin "6") (pinfunction "-IN_6") (pintype "input"))
      (node (ref "R65") (pin "2") (pinfunction "2_2") (pintype "passive"))
      (node (ref "R66") (pin "2") (pinfunction "2_2") (pintype "passive"))
    )
    (net (code "81") (name "Net-(IC2B-OUT)") (class "Default")
      (node (ref "IC2") (pin "7") (pinfunction "OUT_7") (pintype "output"))
      (node (ref "R66") (pin "1") (pinfunction "1_1") (pintype "passive"))
      (node (ref "R67") (pin "1") (pinfunction "1_1") (pintype "passive"))
    )
    (net (code "82") (name "Net-(J1-3)") (class "Default")
      (node (ref "J1") (pin "P$3") (pinfunction "3_P$3") (pintype "passive"))
      (node (ref "R42") (pin "1") (pinfunction "1_1") (pintype "passive"))
    )
    (net (code "83") (name "Net-(J2-3)") (class "Default")
      (node (ref "J2") (pin "P$3") (pinfunction "3_P$3") (pintype "passive"))
      (node (ref "R1") (pin "1") (pinfunction "1_1") (pintype "passive"))
    )
    (net (code "84") (name "Net-(J3-3)") (class "Default")
      (node (ref "J3") (pin "P$3") (pinfunction "3_P$3") (pintype "passive"))
      (node (ref "R41") (pin "1") (pinfunction "1_1") (pintype "passive"))
    )
    (net (code "85") (name "Net-(J4-3)") (class "Default")
      (node (ref "J4") (pin "P$3") (pinfunction "3_P$3") (pintype "passive"))
      (node (ref "R17") (pin "2") (pinfunction "2_2") (pintype "passive"))
    )
    (net (code "86") (name "Net-(J5-3)") (class "Default")
      (node (ref "J5") (pin "P$3") (pinfunction "3_P$3") (pintype "passive"))
      (node (ref "R12") (pin "1") (pinfunction "1_1") (pintype "passive"))
    )
    (net (code "87") (name "Net-(J6-3)") (class "Default")
      (node (ref "J6") (pin "P$3") (pinfunction "3_P$3") (pintype "passive"))
      (node (ref "R67") (pin "2") (pinfunction "2_2") (pintype "passive"))
    )
    (net (code "88") (name "Net-(J8-3)") (class "Default")
      (node (ref "J8") (pin "P$3") (pinfunction "3_P$3") (pintype "passive"))
      (node (ref "R19") (pin "1") (pinfunction "1_1") (pintype "passive"))
    )
    (net (code "89") (name "Net-(J9-3)") (class "Default")
      (node (ref "J9") (pin "P$3") (pinfunction "3_P$3") (pintype "passive"))
      (node (ref "R44") (pin "1") (pinfunction "1_1") (pintype "passive"))
    )
    (net (code "90") (name "Net-(J10-3)") (class "Default")
      (node (ref "J10") (pin "P$3") (pinfunction "3_P$3") (pintype "passive"))
      (node (ref "R47") (pin "1") (pinfunction "1_1") (pintype "passive"))
    )
    (net (code "91") (name "Net-(J11-3)") (class "Default")
      (node (ref "J11") (pin "P$3") (pinfunction "3_P$3") (pintype "passive"))
      (node (ref "R39") (pin "1") (pinfunction "1_1") (pintype "passive"))
    )
    (net (code "92") (name "Net-(J12-3)") (class "Default")
      (node (ref "J12") (pin "P$3") (pinfunction "3_P$3") (pintype "passive"))
      (node (ref "R72") (pin "1") (pinfunction "1_1") (pintype "passive"))
    )
    (net (code "93") (name "Net-(J13-3)") (class "Default")
      (node (ref "J13") (pin "P$3") (pinfunction "3_P$3") (pintype "passive"))
      (node (ref "R69") (pin "1") (pinfunction "1_1") (pintype "passive"))
    )
    (net (code "94") (name "Net-(JP1-Pad5)") (class "Default")
      (node (ref "JP1") (pin "5") (pinfunction "5_5") (pintype "passive"))
      (node (ref "R3") (pin "2") (pinfunction "2_2") (pintype "passive"))
    )
    (net (code "95") (name "Net-(LED2-PadA)") (class "Default")
      (node (ref "LED2") (pin "A") (pinfunction "A_A") (pintype "passive"))
      (node (ref "R50") (pin "2") (pinfunction "2_2") (pintype "passive"))
    )
    (net (code "96") (name "Net-(LED3-PadA)") (class "Default")
      (node (ref "LED3") (pin "A") (pinfunction "A_A") (pintype "passive"))
      (node (ref "R75") (pin "2") (pinfunction "2_2") (pintype "passive"))
    )
    (net (code "97") (name "Net-(LED4-PadA)") (class "Default")
      (node (ref "LED4") (pin "A") (pinfunction "A_A") (pintype "passive"))
      (node (ref "R76") (pin "2") (pinfunction "2_2") (pintype "passive"))
    )
    (net (code "98") (name "Net-(LED5-PadA)") (class "Default")
      (node (ref "LED5") (pin "A") (pinfunction "A_A") (pintype "passive"))
      (node (ref "R77") (pin "2") (pinfunction "2_2") (pintype "passive"))
    )
    (net (code "99") (name "Net-(LED6-C)") (class "Default")
      (node (ref "LED6") (pin "K") (pinfunction "C_K") (pintype "passive"))
      (node (ref "R60") (pin "1") (pinfunction "1_1") (pintype "passive"))
    )
    (net (code "100") (name "Net-(LED7-C)") (class "Default")
      (node (ref "LED7") (pin "K") (pinfunction "C_K") (pintype "passive"))
      (node (ref "R63") (pin "1") (pinfunction "1_1") (pintype "passive"))
    )
    (net (code "101") (name "Net-(LED8-C)") (class "Default")
      (node (ref "LED8") (pin "K") (pinfunction "C_K") (pintype "passive"))
      (node (ref "R10") (pin "2") (pinfunction "2_2") (pintype "passive"))
    )
    (net (code "102") (name "Net-(LED9-C)") (class "Default")
      (node (ref "LED9") (pin "K") (pinfunction "C_K") (pintype "passive"))
      (node (ref "R9") (pin "2") (pinfunction "2_2") (pintype "passive"))
    )
    (net (code "103") (name "Net-(SW1B-A)") (class "Default")
      (node (ref "R4") (pin "2") (pinfunction "2_2") (pintype "passive"))
      (node (ref "SW1") (pin "PL1") (pinfunction "A_PL1") (pintype "passive"))
    )
    (net (code "104") (name "Net-(SW2B-A)") (class "Default")
      (node (ref "R43") (pin "2") (pinfunction "2_2") (pintype "passive"))
      (node (ref "SW2") (pin "PL1") (pinfunction "A_PL1") (pintype "passive"))
    )
    (net (code "105") (name "Net-(SW3B-A)") (class "Default")
      (node (ref "R46") (pin "2") (pinfunction "2_2") (pintype "passive"))
      (node (ref "SW3") (pin "PL1") (pinfunction "A_PL1") (pintype "passive"))
    )
    (net (code "106") (name "Net-(SW4B-A)") (class "Default")
      (node (ref "R49") (pin "2") (pinfunction "2_2") (pintype "passive"))
      (node (ref "SW4") (pin "PL1") (pinfunction "A_PL1") (pintype "passive"))
    )
    (net (code "107") (name "Net-(T1-B)") (class "Default")
      (node (ref "R1") (pin "2") (pinfunction "2_2") (pintype "passive"))
      (node (ref "R2") (pin "2") (pinfunction "2_2") (pintype "passive"))
      (node (ref "T1") (pin "2") (pinfunction "B_2") (pintype "passive"))
    )
    (net (code "108") (name "Net-(T2-B)") (class "Default")
      (node (ref "R19") (pin "2") (pinfunction "2_2") (pintype "passive"))
      (node (ref "R20") (pin "2") (pinfunction "2_2") (pintype "passive"))
      (node (ref "T2") (pin "2") (pinfunction "B_2") (pintype "passive"))
    )
    (net (code "109") (name "Net-(T3-B)") (class "Default")
      (node (ref "R44") (pin "2") (pinfunction "2_2") (pintype "passive"))
      (node (ref "R45") (pin "2") (pinfunction "2_2") (pintype "passive"))
      (node (ref "T3") (pin "2") (pinfunction "B_2") (pintype "passive"))
    )
    (net (code "110") (name "Net-(T4-B)") (class "Default")
      (node (ref "R47") (pin "2") (pinfunction "2_2") (pintype "passive"))
      (node (ref "R48") (pin "2") (pinfunction "2_2") (pintype "passive"))
      (node (ref "T4") (pin "2") (pinfunction "B_2") (pintype "passive"))
    )
    (net (code "111") (name "Net-(T5-B)") (class "Default")
      (node (ref "R55") (pin "1") (pinfunction "1_1") (pintype "passive"))
      (node (ref "T5") (pin "2") (pinfunction "B_2") (pintype "passive"))
    )
    (net (code "112") (name "Net-(T5-C)") (class "Default")
      (node (ref "R12") (pin "2") (pinfunction "2_2") (pintype "passive"))
      (node (ref "R40") (pin "2") (pinfunction "2_2") (pintype "passive"))
      (node (ref "T5") (pin "1") (pinfunction "C_1") (pintype "passive"))
    )
    (net (code "113") (name "Net-(T6-B)") (class "Default")
      (node (ref "R61") (pin "1") (pinfunction "1_1") (pintype "passive"))
      (node (ref "T6") (pin "2") (pinfunction "B_2") (pintype "passive"))
    )
    (net (code "114") (name "Net-(T6-C)") (class "Default")
      (node (ref "R39") (pin "2") (pinfunction "2_2") (pintype "passive"))
      (node (ref "R54") (pin "2") (pinfunction "2_2") (pintype "passive"))
      (node (ref "T6") (pin "1") (pinfunction "C_1") (pintype "passive"))
    )
    (net (code "115") (name "unconnected-(J2-4-PadP$2)") (class "Default")
      (node (ref "J2") (pin "P$2") (pinfunction "4_P$2") (pintype "passive"))
    )
    (net (code "116") (name "unconnected-(J8-4-PadP$2)") (class "Default")
      (node (ref "J8") (pin "P$2") (pinfunction "4_P$2") (pintype "passive"))
    )
    (net (code "117") (name "unconnected-(J9-4-PadP$2)") (class "Default")
      (node (ref "J9") (pin "P$2") (pinfunction "4_P$2") (pintype "passive"))
    )
    (net (code "118") (name "unconnected-(J10-4-PadP$2)") (class "Default")
      (node (ref "J10") (pin "P$2") (pinfunction "4_P$2") (pintype "passive"))
    )
    (net (code "119") (name "unconnected-(X3-S1-PadM1)") (class "Default")
      (node (ref "X3") (pin "M1") (pinfunction "S1_M1") (pintype "passive"))
    )
    (net (code "120") (name "unconnected-(X3-S2-PadM2)") (class "Default")
      (node (ref "X3") (pin "M2") (pinfunction "S2_M2") (pintype "passive"))
    )
  )
)
